# Project_Board.net
KiCad netlist of a schematic drawn in Altium Designer
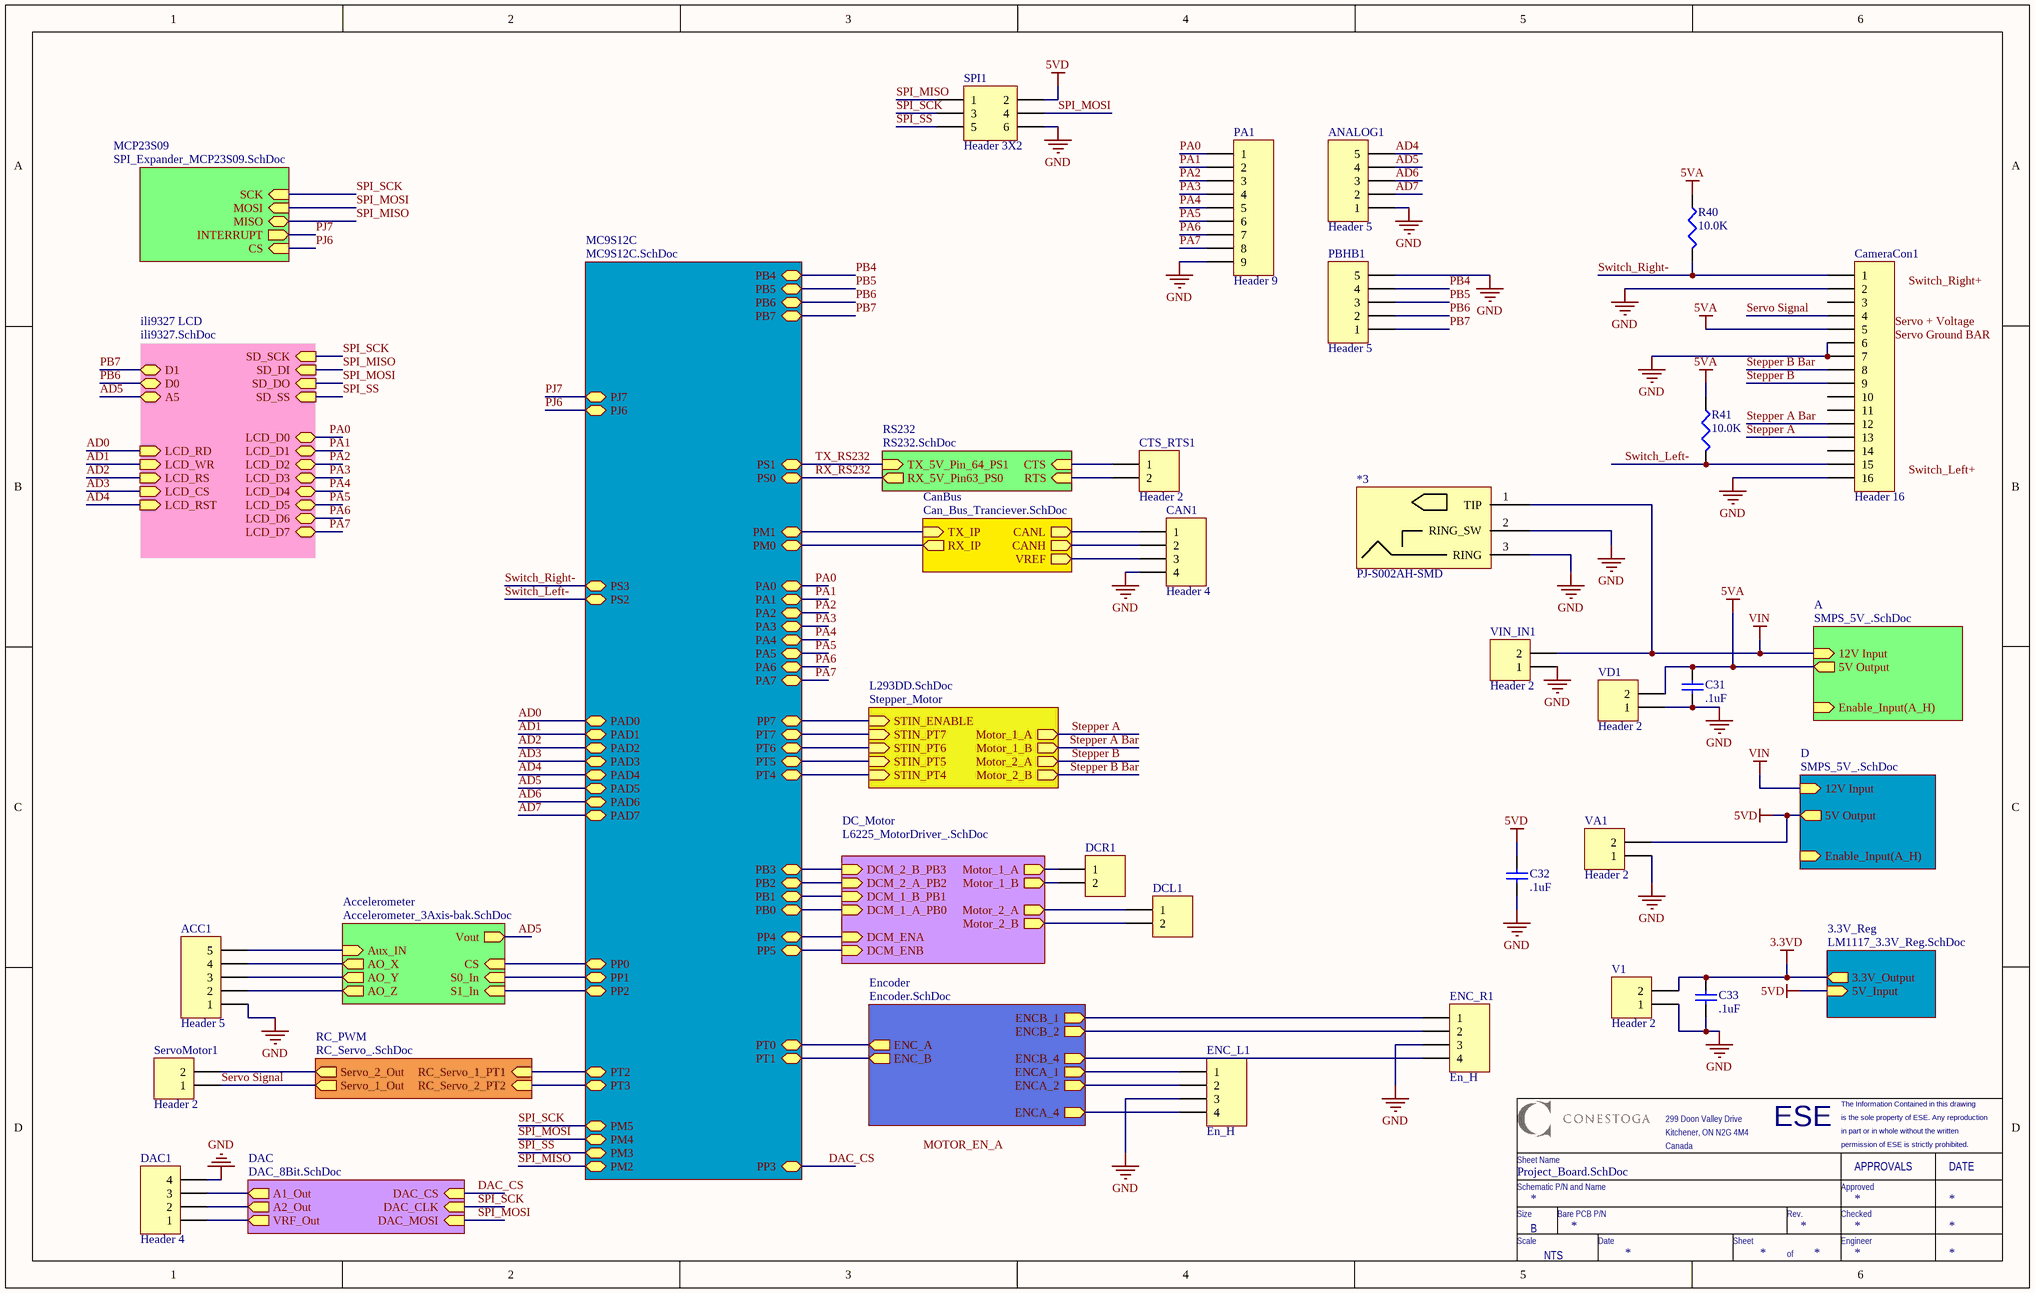
[diagram p0: Project_Board.SchDoc]

(export (version "E")
  (design (tool "Eeschema 10.0.6"))
  (components
    (comp (ref "*3")
      (value "PJ-S002AH-SMD")
      (footprint "PJ-002AH-SMD")
      (libsource (lib "Crystal") (part "PJ-S002AH-SMD"))
    )
    (comp (ref "ACC1")
      (value "Header 5")
      (footprint "HDR1X5")
      (description "Header, 5-Pin")
      (fields (field (name "PUBLISHER") "Altium Limited"))
      (libsource (lib "Miscellaneous Connectors") (part "Header 5"))
    )
    (comp (ref "ANALOG1")
      (value "Header 5")
      (footprint "HDR1X5")
      (description "Header, 5-Pin")
      (fields (field (name "PUBLISHER") "Altium Limited"))
      (libsource (lib "Miscellaneous Connectors") (part "Header 5"))
    )
    (comp (ref "C31")
      (value ".1uF")
      (footprint "CAPC2012X09M")
      (description "CAP CER .1uF 50v Z5U 0805")
      (fields (field (name "TOLERANCE") "±20%") (field (name "MPN") "C0805C104M5UACTU"))
      (libsource (lib "esd_library") (part "CAP-Z5U-.1uF-50V-±20%"))
    )
    (comp (ref "C32")
      (value ".1uF")
      (footprint "CAPC2012X09M")
      (description "CAP CER .1uF 50v Z5U 0805")
      (fields (field (name "TOLERANCE") "±20%") (field (name "MPN") "C0805C104M5UACTU"))
      (libsource (lib "esd_library") (part "CAP-Z5U-.1uF-50V-±20%"))
    )
    (comp (ref "C33")
      (value ".1uF")
      (footprint "CAPC2012X09M")
      (description "CAP CER .1uF 50v Z5U 0805")
      (fields (field (name "TOLERANCE") "±20%") (field (name "MPN") "C0805C104M5UACTU"))
      (libsource (lib "esd_library") (part "CAP-Z5U-.1uF-50V-±20%"))
    )
    (comp (ref "CameraCon1")
      (value "Header 16")
      (footprint "HDR1X16")
      (description "Header, 16-Pin")
      (fields (field (name "PUBLISHER") "Altium Limited"))
      (libsource (lib "Miscellaneous Connectors") (part "Header 16"))
    )
    (comp (ref "CAN1")
      (value "Header 4")
      (footprint "HDR1X4")
      (description "Header, 4-Pin")
      (fields (field (name "PUBLISHER") "Altium Limited"))
      (libsource (lib "Miscellaneous Connectors") (part "Header 4"))
    )
    (comp (ref "CTS_RTS1")
      (value "Header 2")
      (footprint "HDR1X2")
      (description "Header, 2-Pin")
      (libsource (lib "") (part "Header 2_1"))
    )
    (comp (ref "DAC1")
      (value "Header 4")
      (footprint "HDR1X4")
      (description "Header, 4-Pin")
      (fields (field (name "PUBLISHER") "Altium Limited"))
      (libsource (lib "") (part "Header 4_1"))
    )
    (comp (ref "DCL1")
      (value "Header 2")
      (footprint "HDR1X2")
      (description "Header, 2-Pin")
      (fields (field (name "MPN") "PEC02SFAN"))
      (libsource (lib "") (part "Header 2_1"))
    )
    (comp (ref "DCR1")
      (value "Header 2")
      (footprint "HDR1X2")
      (description "Header, 2-Pin")
      (fields (field (name "MPN") "PEC02SFAN"))
      (libsource (lib "") (part "Header 2_1"))
    )
    (comp (ref "ENC_L1")
      (value "En_H")
      (footprint "HDR1X4")
      (description "Header, 4-Pin")
      (fields (field (name "PUBLISHER") "Altium Limited"))
      (libsource (lib "Miscellaneous Connectors") (part "Header 4"))
    )
    (comp (ref "ENC_R1")
      (value "En_H")
      (footprint "HDR1X4")
      (description "Header, 4-Pin")
      (fields (field (name "PUBLISHER") "Altium Limited"))
      (libsource (lib "Miscellaneous Connectors") (part "Header 4"))
    )
    (comp (ref "PA1")
      (value "Header 9")
      (footprint "HDR1X9")
      (description "Header, 9-Pin")
      (fields (field (name "PUBLISHER") "Altium Limited"))
      (libsource (lib "Miscellaneous Connectors") (part "Header 9"))
    )
    (comp (ref "PBHB1")
      (value "Header 5")
      (footprint "HDR1X5")
      (description "Header, 5-Pin")
      (fields (field (name "PUBLISHER") "Altium Limited"))
      (libsource (lib "Miscellaneous Connectors") (part "Header 5"))
    )
    (comp (ref "R40")
      (value "10.0K")
      (footprint "RESC2112X05M")
      (description "RES SMD 10.0K OHM 1% 1/8W 0805")
      (fields (field (name "MPN") "CRCW080510K0FKEA") (field (name "Comment") "Res3"))
      (libsource (lib "esd_library") (part "Resistor_10.0K"))
    )
    (comp (ref "R41")
      (value "10.0K")
      (footprint "RESC2112X05M")
      (description "RES SMD 10.0K OHM 1% 1/8W 0805")
      (fields (field (name "MPN") "CRCW080510K0FKEA") (field (name "Comment") "Res3"))
      (libsource (lib "esd_library") (part "Resistor_10.0K"))
    )
    (comp (ref "ServoMotor1")
      (value "Header 2")
      (footprint "HDR1X2")
      (description "Header, 2-Pin")
      (libsource (lib "esd_library") (part "Header 2"))
    )
    (comp (ref "SPI1")
      (value "Header 3X2")
      (footprint "HDR2X3")
      (description "Header, 3-Pin, Dual row")
      (fields (field (name "PUBLISHER") "Altium Limited"))
      (libsource (lib "Miscellaneous Connectors") (part "Header 3X2"))
    )
    (comp (ref "V1")
      (value "Header 2")
      (footprint "HDR1X2")
      (description "Header, 2-Pin")
      (libsource (lib "esd_library") (part "Header 2"))
    )
    (comp (ref "VA1")
      (value "Header 2")
      (footprint "HDR1X2")
      (description "Header, 2-Pin")
      (libsource (lib "esd_library") (part "Header 2"))
    )
    (comp (ref "VD1")
      (value "Header 2")
      (footprint "HDR1X2")
      (description "Header, 2-Pin")
      (libsource (lib "esd_library") (part "Header 2"))
    )
    (comp (ref "VIN_IN1")
      (value "Header 2")
      (footprint "HDR1X2")
      (description "Header, 2-Pin")
      (libsource (lib "esd_library") (part "Header 2"))
    )
  )
  (nets
    (net (code "1") (name "/A1_Out") (class "Default")
      (node (ref "DAC1") (pin "3") (pinfunction "3_3") (pintype "passive"))
    )
    (net (code "2") (name "/A2_Out") (class "Default")
      (node (ref "DAC1") (pin "2") (pinfunction "2_2") (pintype "passive"))
    )
    (net (code "7") (name "/AD4") (class "Default")
      (node (ref "ANALOG1") (pin "5") (pinfunction "5_5") (pintype "passive"))
    )
    (net (code "8") (name "/AD5") (class "Default")
      (node (ref "ANALOG1") (pin "4") (pinfunction "4_4") (pintype "passive"))
    )
    (net (code "9") (name "/AD6") (class "Default")
      (node (ref "ANALOG1") (pin "3") (pinfunction "3_3") (pintype "passive"))
    )
    (net (code "10") (name "/AD7") (class "Default")
      (node (ref "ANALOG1") (pin "2") (pinfunction "2_2") (pintype "passive"))
    )
    (net (code "11") (name "/AO_X") (class "Default")
      (node (ref "ACC1") (pin "4") (pinfunction "4_4") (pintype "passive"))
    )
    (net (code "12") (name "/AO_Y") (class "Default")
      (node (ref "ACC1") (pin "3") (pinfunction "3_3") (pintype "passive"))
    )
    (net (code "13") (name "/AO_Z") (class "Default")
      (node (ref "ACC1") (pin "2") (pinfunction "2_2") (pintype "passive"))
    )
    (net (code "14") (name "/Aux_IN") (class "Default")
      (node (ref "ACC1") (pin "5") (pinfunction "5_5") (pintype "passive"))
    )
    (net (code "15") (name "/CANH") (class "Default")
      (node (ref "CAN1") (pin "2") (pinfunction "2_2") (pintype "passive"))
    )
    (net (code "16") (name "/CANL") (class "Default")
      (node (ref "CAN1") (pin "1") (pinfunction "1_1") (pintype "passive"))
    )
    (net (code "18") (name "/CTS") (class "Default")
      (node (ref "CTS_RTS1") (pin "1") (pinfunction "1_1") (pintype "passive"))
    )
    (net (code "26") (name "/ENCA_1") (class "Default")
      (node (ref "ENC_L1") (pin "1") (pinfunction "1_1") (pintype "passive"))
    )
    (net (code "27") (name "/ENCA_2") (class "Default")
      (node (ref "ENC_L1") (pin "2") (pinfunction "2_2") (pintype "passive"))
    )
    (net (code "28") (name "/ENCA_4") (class "Default")
      (node (ref "ENC_L1") (pin "4") (pinfunction "4_4") (pintype "passive"))
    )
    (net (code "29") (name "/ENCB_1") (class "Default")
      (node (ref "ENC_R1") (pin "1") (pinfunction "1_1") (pintype "passive"))
    )
    (net (code "30") (name "/ENCB_2") (class "Default")
      (node (ref "ENC_R1") (pin "2") (pinfunction "2_2") (pintype "passive"))
    )
    (net (code "31") (name "/ENCB_4") (class "Default")
      (node (ref "ENC_R1") (pin "4") (pinfunction "4_4") (pintype "passive"))
    )
    (net (code "37") (name "/Motor_1_A") (class "Default")
      (node (ref "DCR1") (pin "1") (pinfunction "1_1") (pintype "passive"))
    )
    (net (code "38") (name "/Motor_1_B") (class "Default")
      (node (ref "DCR1") (pin "2") (pinfunction "2_2") (pintype "passive"))
    )
    (net (code "39") (name "/Motor_2_A") (class "Default")
      (node (ref "DCL1") (pin "1") (pinfunction "1_1") (pintype "passive"))
    )
    (net (code "40") (name "/Motor_2_B") (class "Default")
      (node (ref "DCL1") (pin "2") (pinfunction "2_2") (pintype "passive"))
    )
    (net (code "41") (name "/PA0") (class "Default")
      (node (ref "PA1") (pin "1") (pinfunction "1_1") (pintype "passive"))
    )
    (net (code "42") (name "/PA1") (class "Default")
      (node (ref "PA1") (pin "2") (pinfunction "2_2") (pintype "passive"))
    )
    (net (code "43") (name "/PA2") (class "Default")
      (node (ref "PA1") (pin "3") (pinfunction "3_3") (pintype "passive"))
    )
    (net (code "44") (name "/PA3") (class "Default")
      (node (ref "PA1") (pin "4") (pinfunction "4_4") (pintype "passive"))
    )
    (net (code "45") (name "/PA4") (class "Default")
      (node (ref "PA1") (pin "5") (pinfunction "5_5") (pintype "passive"))
    )
    (net (code "46") (name "/PA5") (class "Default")
      (node (ref "PA1") (pin "6") (pinfunction "6_6") (pintype "passive"))
    )
    (net (code "47") (name "/PA6") (class "Default")
      (node (ref "PA1") (pin "7") (pinfunction "7_7") (pintype "passive"))
    )
    (net (code "48") (name "/PA7") (class "Default")
      (node (ref "PA1") (pin "8") (pinfunction "8_8") (pintype "passive"))
    )
    (net (code "49") (name "/PB4") (class "Default")
      (node (ref "PBHB1") (pin "4") (pinfunction "4_4") (pintype "passive"))
    )
    (net (code "50") (name "/PB5") (class "Default")
      (node (ref "PBHB1") (pin "3") (pinfunction "3_3") (pintype "passive"))
    )
    (net (code "51") (name "/PB6") (class "Default")
      (node (ref "PBHB1") (pin "2") (pinfunction "2_2") (pintype "passive"))
    )
    (net (code "52") (name "/PB7") (class "Default")
      (node (ref "PBHB1") (pin "1") (pinfunction "1_1") (pintype "passive"))
    )
    (net (code "65") (name "/RTS") (class "Default")
      (node (ref "CTS_RTS1") (pin "2") (pinfunction "2_2") (pintype "passive"))
    )
    (net (code "68") (name "/SPI_MISO") (class "Default")
      (node (ref "SPI1") (pin "1") (pinfunction "1_1") (pintype "passive"))
    )
    (net (code "69") (name "/SPI_MOSI") (class "Default")
      (node (ref "SPI1") (pin "4") (pinfunction "4_4") (pintype "passive"))
    )
    (net (code "70") (name "/SPI_SCK") (class "Default")
      (node (ref "SPI1") (pin "3") (pinfunction "3_3") (pintype "passive"))
    )
    (net (code "71") (name "/SPI_SS") (class "Default")
      (node (ref "SPI1") (pin "5") (pinfunction "5_5") (pintype "passive"))
    )
    (net (code "74") (name "/Servo Signal") (class "Default")
      (node (ref "CameraCon1") (pin "4") (pinfunction "4_4") (pintype "passive"))
      (node (ref "ServoMotor1") (pin "1") (pinfunction "1_1") (pintype "passive"))
    )
    (net (code "75") (name "/Servo_2_Out") (class "Default")
      (node (ref "ServoMotor1") (pin "2") (pinfunction "2_2") (pintype "passive"))
    )
    (net (code "76") (name "/Stepper A") (class "Default")
      (node (ref "CameraCon1") (pin "13") (pinfunction "13_13") (pintype "passive"))
    )
    (net (code "77") (name "/Stepper A Bar") (class "Default")
      (node (ref "CameraCon1") (pin "12") (pinfunction "12_12") (pintype "passive"))
    )
    (net (code "78") (name "/Stepper B") (class "Default")
      (node (ref "CameraCon1") (pin "9") (pinfunction "9_9") (pintype "passive"))
    )
    (net (code "79") (name "/Stepper B Bar") (class "Default")
      (node (ref "CameraCon1") (pin "8") (pinfunction "8_8") (pintype "passive"))
    )
    (net (code "81") (name "/Switch_Left-") (class "Default")
      (node (ref "CameraCon1") (pin "15") (pinfunction "15_15") (pintype "passive"))
      (node (ref "R41") (pin "2") (pinfunction "2_2") (pintype "passive"))
    )
    (net (code "83") (name "/Switch_Right-") (class "Default")
      (node (ref "CameraCon1") (pin "1") (pinfunction "1_1") (pintype "passive"))
      (node (ref "R40") (pin "2") (pinfunction "2_2") (pintype "passive"))
    )
    (net (code "85") (name "/VREF") (class "Default")
      (node (ref "CAN1") (pin "3") (pinfunction "3_3") (pintype "passive"))
    )
    (net (code "86") (name "/VRF_Out") (class "Default")
      (node (ref "DAC1") (pin "1") (pinfunction "1_1") (pintype "passive"))
    )
    (net (code "87") (name "3.3VD") (class "Default")
      (node (ref "C33") (pin "2") (pinfunction "2_2") (pintype "passive"))
      (node (ref "V1") (pin "2") (pinfunction "2_2") (pintype "passive"))
    )
    (net (code "88") (name "5VA") (class "Default")
      (node (ref "C31") (pin "2") (pinfunction "2_2") (pintype "passive"))
      (node (ref "CameraCon1") (pin "5") (pinfunction "5_5") (pintype "passive"))
      (node (ref "R40") (pin "1") (pinfunction "1_1") (pintype "passive"))
      (node (ref "R41") (pin "1") (pinfunction "1_1") (pintype "passive"))
      (node (ref "VD1") (pin "2") (pinfunction "2_2") (pintype "passive"))
    )
    (net (code "89") (name "5VD") (class "Default")
      (node (ref "C32") (pin "2") (pinfunction "2_2") (pintype "passive"))
      (node (ref "SPI1") (pin "2") (pinfunction "2_2") (pintype "passive"))
      (node (ref "VA1") (pin "2") (pinfunction "2_2") (pintype "passive"))
    )
    (net (code "90") (name "GND") (class "Default")
      (node (ref "*3") (pin "2") (pinfunction "RING_SW_2") (pintype "passive"))
      (node (ref "*3") (pin "3") (pinfunction "RING_3") (pintype "passive"))
      (node (ref "ACC1") (pin "1") (pinfunction "1_1") (pintype "passive"))
      (node (ref "ANALOG1") (pin "1") (pinfunction "1_1") (pintype "passive"))
      (node (ref "C31") (pin "1") (pinfunction "1_1") (pintype "passive"))
      (node (ref "C32") (pin "1") (pinfunction "1_1") (pintype "passive"))
      (node (ref "C33") (pin "1") (pinfunction "1_1") (pintype "passive"))
      (node (ref "CAN1") (pin "4") (pinfunction "4_4") (pintype "passive"))
      (node (ref "CameraCon1") (pin "16") (pinfunction "16_16") (pintype "passive"))
      (node (ref "CameraCon1") (pin "2") (pinfunction "2_2") (pintype "passive"))
      (node (ref "CameraCon1") (pin "6") (pinfunction "6_6") (pintype "passive"))
      (node (ref "CameraCon1") (pin "7") (pinfunction "7_7") (pintype "passive"))
      (node (ref "DAC1") (pin "4") (pinfunction "4_4") (pintype "passive"))
      (node (ref "ENC_L1") (pin "3") (pinfunction "3_3") (pintype "passive"))
      (node (ref "ENC_R1") (pin "3") (pinfunction "3_3") (pintype "passive"))
      (node (ref "PA1") (pin "9") (pinfunction "9_9") (pintype "passive"))
      (node (ref "PBHB1") (pin "5") (pinfunction "5_5") (pintype "passive"))
      (node (ref "SPI1") (pin "6") (pinfunction "6_6") (pintype "passive"))
      (node (ref "V1") (pin "1") (pinfunction "1_1") (pintype "passive"))
      (node (ref "VA1") (pin "1") (pinfunction "1_1") (pintype "passive"))
      (node (ref "VD1") (pin "1") (pinfunction "1_1") (pintype "passive"))
      (node (ref "VIN_IN1") (pin "1") (pinfunction "1_1") (pintype "passive"))
    )
    (net (code "91") (name "VIN") (class "Default")
      (node (ref "*3") (pin "1") (pinfunction "TIP_1") (pintype "passive"))
      (node (ref "VIN_IN1") (pin "2") (pinfunction "2_2") (pintype "passive"))
    )
    (net (code "92") (name "unconnected-(CameraCon1-Pad3)") (class "Default")
      (node (ref "CameraCon1") (pin "3") (pinfunction "3_3") (pintype "passive"))
    )
    (net (code "93") (name "unconnected-(CameraCon1-Pad10)") (class "Default")
      (node (ref "CameraCon1") (pin "10") (pinfunction "10_10") (pintype "passive"))
    )
    (net (code "94") (name "unconnected-(CameraCon1-Pad11)") (class "Default")
      (node (ref "CameraCon1") (pin "11") (pinfunction "11_11") (pintype "passive"))
    )
    (net (code "95") (name "unconnected-(CameraCon1-Pad14)") (class "Default")
      (node (ref "CameraCon1") (pin "14") (pinfunction "14_14") (pintype "passive"))
    )
  )
)
